# Dashboard_Tester_rev1.net
KiCad netlist of a schematic drawn in EAGLE
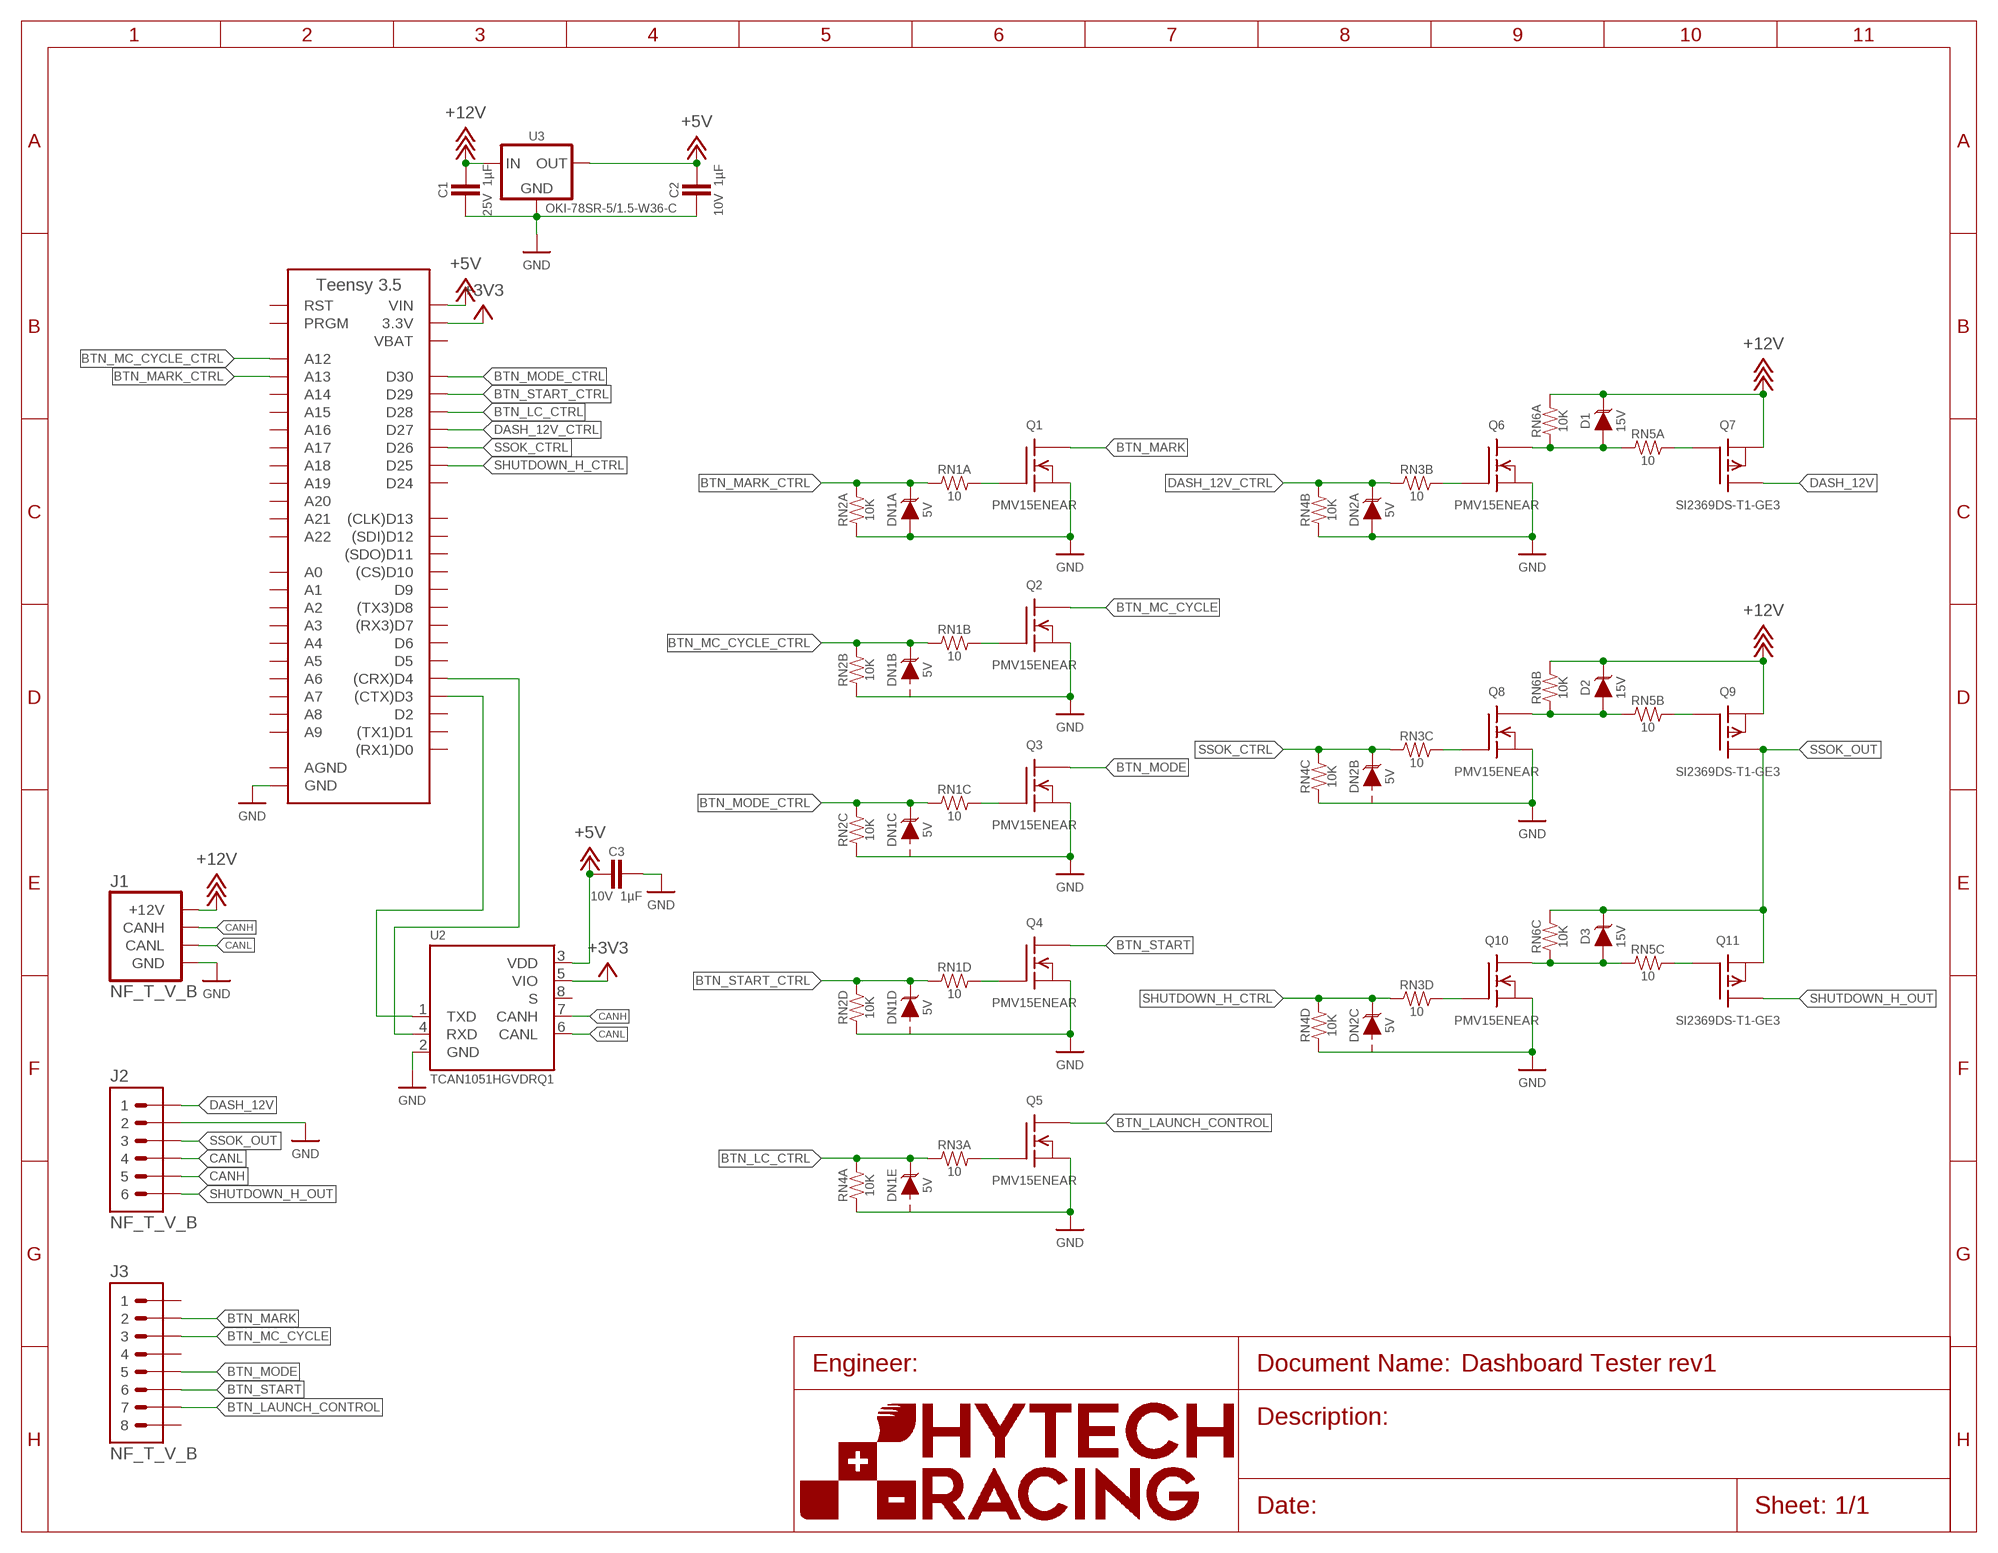
[diagram p0: schematic, sheet 1]

(export (version "E")
  (design (tool "Eeschema 10.0.6"))
  (components
    (comp (ref "C1")
      (value "CAPACITOR_0603_25V_1UF")
      (footprint "eagle-import:0603-CAP")
      (fields
        (field (name "CAPACITANCE") "1µF")
        (field (name "MANUFACTURER") "Samsung Electro-Mechanics")
        (field (name "MPN") "CL10B105KA8NNNC")
        (field (name "TOLERANCE") "10%")
        (field (name "VOLTAGE") "25V")
      )
      (libsource (lib "eagle-import") (part "CAPACITOR_?_060325V_1UF"))
    )
    (comp (ref "C2")
      (value "CAPACITOR_0603_10V_1UF")
      (footprint "eagle-import:0603-CAP")
      (fields
        (field (name "CAPACITANCE") "1µF")
        (field (name "MANUFACTURER") "Yageo")
        (field (name "MPN") "CC0603KRX7R6BB105")
        (field (name "TOLERANCE") "10%")
        (field (name "VOLTAGE") "10V")
      )
      (libsource (lib "eagle-import") (part "CAPACITOR_?_060310V_1UF"))
    )
    (comp (ref "C3")
      (value "CAPACITOR_0603_10V_1UF")
      (footprint "eagle-import:0603-CAP")
      (fields
        (field (name "CAPACITANCE") "1µF")
        (field (name "MANUFACTURER") "Yageo")
        (field (name "MPN") "CC0603KRX7R6BB105")
        (field (name "TOLERANCE") "10%")
        (field (name "VOLTAGE") "10V")
      )
      (libsource (lib "eagle-import") (part "CAPACITOR_?_060310V_1UF"))
    )
    (comp (ref "D1")
      (value "TVS_15V")
      (footprint "eagle-import:SOT-23")
      (fields
        (field (name "MANUFACTURER") "Vishay General Semiconductor - Diodes Division")
        (field (name "MPN") "GSOT15-E3-08")
        (field (name "VOLTAGE") "15V")
      )
      (libsource (lib "eagle-import") (part "TVS_15V"))
    )
    (comp (ref "D2")
      (value "TVS_15V")
      (footprint "eagle-import:SOT-23")
      (fields
        (field (name "MANUFACTURER") "Vishay General Semiconductor - Diodes Division")
        (field (name "MPN") "GSOT15-E3-08")
        (field (name "VOLTAGE") "15V")
      )
      (libsource (lib "eagle-import") (part "TVS_15V"))
    )
    (comp (ref "D3")
      (value "TVS_15V")
      (footprint "eagle-import:SOT-23")
      (fields
        (field (name "MANUFACTURER") "Vishay General Semiconductor - Diodes Division")
        (field (name "MPN") "GSOT15-E3-08")
        (field (name "VOLTAGE") "15V")
      )
      (libsource (lib "eagle-import") (part "TVS_15V"))
    )
    (comp (ref "DN1")
      (value "TVS_ARRAY_5V")
      (footprint "eagle-import:SOT363")
      (fields
        (field (name "MANUFACTURER") "Vishay General Semiconductor - Diodes Division")
        (field (name "MPN") "VESD05A5-06G-G3-08")
        (field (name "VOLTAGE") "5V")
      )
      (libsource (lib "eagle-import") (part "TVS_ARRAY_5V"))
    )
    (comp (ref "DN2")
      (value "TVS_ARRAY_5V")
      (footprint "eagle-import:SOT363")
      (fields
        (field (name "MANUFACTURER") "Vishay General Semiconductor - Diodes Division")
        (field (name "MPN") "VESD05A5-06G-G3-08")
        (field (name "VOLTAGE") "5V")
      )
      (libsource (lib "eagle-import") (part "TVS_ARRAY_5V"))
    )
    (comp (ref "J1")
      (value "CONNECTOR-CAN_NF_T_V_BLACK")
      (footprint "eagle-import:MOLEX_NANOFIT_PTH_04")
      (fields
        (field (name "MANUFACTURER") "Molex")
        (field (name "MODEL") "NF_T_V_B")
        (field (name "MPN") "105429-1304 ")
      )
      (libsource (lib "eagle-import") (part "CONNECTOR-CAN_?_NF_T_VBLACK"))
    )
    (comp (ref "J2")
      (value "CONNECTOR-6_NF_T_V_BLACK")
      (footprint "eagle-import:MOLEX_NANOFIT_PTH_06")
      (fields
        (field (name "MANUFACTURER") "Molex")
        (field (name "MODEL") "NF_T_V_B")
        (field (name "MPN") "105310-1306 ")
      )
      (libsource (lib "eagle-import") (part "CONNECTOR-6_?_NF_T_VBLACK"))
    )
    (comp (ref "J3")
      (value "CONNECTOR-8_NF_T_V_BLACK")
      (footprint "eagle-import:MOLEX_NANOFIT_PTH_08")
      (fields
        (field (name "MANUFACTURER") "Molex")
        (field (name "MODEL") "NF_T_V_B")
        (field (name "MPN") "105310-1308")
      )
      (libsource (lib "eagle-import") (part "CONNECTOR-8_?_NF_T_VBLACK"))
    )
    (comp (ref "Q1")
      (value "TRANSISTOR_N_MOS_PMV15ENEA")
      (footprint "eagle-import:SOT-23")
      (fields (field (name "MANUFACTURER") "Nexperia USA Inc.") (field (name "MPN") "PMV15ENEAR"))
      (libsource (lib "eagle-import") (part "TRANSISTOR_N_MOS_PMV15ENEA"))
    )
    (comp (ref "Q2")
      (value "TRANSISTOR_N_MOS_PMV15ENEA")
      (footprint "eagle-import:SOT-23")
      (fields (field (name "MANUFACTURER") "Nexperia USA Inc.") (field (name "MPN") "PMV15ENEAR"))
      (libsource (lib "eagle-import") (part "TRANSISTOR_N_MOS_PMV15ENEA"))
    )
    (comp (ref "Q3")
      (value "TRANSISTOR_N_MOS_PMV15ENEA")
      (footprint "eagle-import:SOT-23")
      (fields (field (name "MANUFACTURER") "Nexperia USA Inc.") (field (name "MPN") "PMV15ENEAR"))
      (libsource (lib "eagle-import") (part "TRANSISTOR_N_MOS_PMV15ENEA"))
    )
    (comp (ref "Q4")
      (value "TRANSISTOR_N_MOS_PMV15ENEA")
      (footprint "eagle-import:SOT-23")
      (fields (field (name "MANUFACTURER") "Nexperia USA Inc.") (field (name "MPN") "PMV15ENEAR"))
      (libsource (lib "eagle-import") (part "TRANSISTOR_N_MOS_PMV15ENEA"))
    )
    (comp (ref "Q5")
      (value "TRANSISTOR_N_MOS_PMV15ENEA")
      (footprint "eagle-import:SOT-23")
      (fields (field (name "MANUFACTURER") "Nexperia USA Inc.") (field (name "MPN") "PMV15ENEAR"))
      (libsource (lib "eagle-import") (part "TRANSISTOR_N_MOS_PMV15ENEA"))
    )
    (comp (ref "Q6")
      (value "TRANSISTOR_N_MOS_PMV15ENEA")
      (footprint "eagle-import:SOT-23")
      (fields (field (name "MANUFACTURER") "Nexperia USA Inc.") (field (name "MPN") "PMV15ENEAR"))
      (libsource (lib "eagle-import") (part "TRANSISTOR_N_MOS_PMV15ENEA"))
    )
    (comp (ref "Q7")
      (value "TRANSISTOR_P_MOS_SOT23_SI2369DS-T1-GE3")
      (footprint "eagle-import:SOT-23")
      (fields (field (name "MANUFACTURER") "Vishay Siliconix") (field (name "MPN") "SI2369DS-T1-GE3"))
      (libsource (lib "eagle-import") (part "TRANSISTOR_P_MOS_?_SOT23SI2369DS-T1-GE3"))
    )
    (comp (ref "Q8")
      (value "TRANSISTOR_N_MOS_PMV15ENEA")
      (footprint "eagle-import:SOT-23")
      (fields (field (name "MANUFACTURER") "Nexperia USA Inc.") (field (name "MPN") "PMV15ENEAR"))
      (libsource (lib "eagle-import") (part "TRANSISTOR_N_MOS_PMV15ENEA"))
    )
    (comp (ref "Q9")
      (value "TRANSISTOR_P_MOS_SOT23_SI2369DS-T1-GE3")
      (footprint "eagle-import:SOT-23")
      (fields (field (name "MANUFACTURER") "Vishay Siliconix") (field (name "MPN") "SI2369DS-T1-GE3"))
      (libsource (lib "eagle-import") (part "TRANSISTOR_P_MOS_?_SOT23SI2369DS-T1-GE3"))
    )
    (comp (ref "Q10")
      (value "TRANSISTOR_N_MOS_PMV15ENEA")
      (footprint "eagle-import:SOT-23")
      (fields (field (name "MANUFACTURER") "Nexperia USA Inc.") (field (name "MPN") "PMV15ENEAR"))
      (libsource (lib "eagle-import") (part "TRANSISTOR_N_MOS_PMV15ENEA"))
    )
    (comp (ref "Q11")
      (value "TRANSISTOR_P_MOS_SOT23_SI2369DS-T1-GE3")
      (footprint "eagle-import:SOT-23")
      (fields (field (name "MANUFACTURER") "Vishay Siliconix") (field (name "MPN") "SI2369DS-T1-GE3"))
      (libsource (lib "eagle-import") (part "TRANSISTOR_P_MOS_?_SOT23SI2369DS-T1-GE3"))
    )
    (comp (ref "RN1")
      (value "RESISTOR_NETWORK_4_10")
      (footprint "eagle-import:1206-RES")
      (fields
        (field (name "MANUFACTURER") "Bourns Inc.")
        (field (name "MPN") "CAT16-100J4LF")
        (field (name "RESISTANCE") "10")
      )
      (libsource (lib "eagle-import") (part "RESISTOR_NETWORK_4_10"))
    )
    (comp (ref "RN2")
      (value "RESISTOR_NETWORK_4_10K")
      (footprint "eagle-import:1206-RES")
      (fields
        (field (name "MANUFACTURER") "Yageo")
        (field (name "MPN") "TC164-FR-0710KL")
        (field (name "RESISTANCE") "10K")
      )
      (libsource (lib "eagle-import") (part "RESISTOR_NETWORK_4_10K"))
    )
    (comp (ref "RN3")
      (value "RESISTOR_NETWORK_4_10")
      (footprint "eagle-import:1206-RES")
      (fields
        (field (name "MANUFACTURER") "Bourns Inc.")
        (field (name "MPN") "CAT16-100J4LF")
        (field (name "RESISTANCE") "10")
      )
      (libsource (lib "eagle-import") (part "RESISTOR_NETWORK_4_10"))
    )
    (comp (ref "RN4")
      (value "RESISTOR_NETWORK_4_10K")
      (footprint "eagle-import:1206-RES")
      (fields
        (field (name "MANUFACTURER") "Yageo")
        (field (name "MPN") "TC164-FR-0710KL")
        (field (name "RESISTANCE") "10K")
      )
      (libsource (lib "eagle-import") (part "RESISTOR_NETWORK_4_10K"))
    )
    (comp (ref "RN5")
      (value "RESISTOR_NETWORK_4_10")
      (footprint "eagle-import:1206-RES")
      (fields
        (field (name "MANUFACTURER") "Bourns Inc.")
        (field (name "MPN") "CAT16-100J4LF")
        (field (name "RESISTANCE") "10")
      )
      (libsource (lib "eagle-import") (part "RESISTOR_NETWORK_4_10"))
    )
    (comp (ref "RN6")
      (value "RESISTOR_NETWORK_4_10K")
      (footprint "eagle-import:1206-RES")
      (fields
        (field (name "MANUFACTURER") "Yageo")
        (field (name "MPN") "TC164-FR-0710KL")
        (field (name "RESISTANCE") "10K")
      )
      (libsource (lib "eagle-import") (part "RESISTOR_NETWORK_4_10K"))
    )
    (comp (ref "U1")
      (value "TEENSY_3.5")
      (footprint "eagle-import:TEENSY_LONG_EXT")
      (libsource (lib "eagle-import") (part "TEENSY_3.5"))
    )
    (comp (ref "U2")
      (value "CAN_TRANSCIEVER_TCAN1051HQV-Q1")
      (footprint "eagle-import:SOIC-08")
      (fields (field (name "MANUFACTURER") "Texas Instruments") (field (name "MPN") "TCAN1051HGVDRQ1"))
      (libsource (lib "eagle-import") (part "CAN_TRANSCIEVER_TCAN1051V-Q1HQ"))
    )
    (comp (ref "U3")
      (value "VOLTAGE_REGULATOR_OKI-78SR_5V")
      (footprint "eagle-import:OKI-78SR")
      (fields
        (field (name "MANUFACTURER") "Murata Power Solutions Inc.")
        (field (name "MPN") "OKI-78SR-5/1.5-W36-C")
      )
      (libsource (lib "eagle-import") (part "VOLTAGE_REGULATOR_?_OKI-78SR5V"))
    )
  )
  (nets
    (net (code "1") (name "+3V3") (class "Default")
      (node (ref "U1") (pin "3V3") (pinfunction "3.3V_3V3") (pintype "power_in"))
      (node (ref "U1") (pin "3V3@2") (pinfunction "3.3V_3V3@2") (pintype "power_in"))
      (node (ref "U1") (pin "3V3@3") (pinfunction "3.3V_3V3@3") (pintype "power_in"))
      (node (ref "U2") (pin "5") (pinfunction "VIO_5") (pintype "power_in"))
    )
    (net (code "2") (name "+5V") (class "Default")
      (node (ref "C2") (pin "1") (pinfunction "1_1") (pintype "passive"))
      (node (ref "C3") (pin "2") (pinfunction "2_2") (pintype "passive"))
      (node (ref "U1") (pin "VIN") (pinfunction "VIN_VIN") (pintype "power_in"))
      (node (ref "U2") (pin "3") (pinfunction "VDD_3") (pintype "power_in"))
      (node (ref "U3") (pin "3") (pinfunction "OUT_3") (pintype "power_in"))
    )
    (net (code "3") (name "+12V") (class "Default")
      (node (ref "C1") (pin "1") (pinfunction "1_1") (pintype "passive"))
      (node (ref "D1") (pin "3") (pinfunction "C_3") (pintype "passive"))
      (node (ref "D2") (pin "3") (pinfunction "C_3") (pintype "passive"))
      (node (ref "J1") (pin "1") (pinfunction "+12V_1") (pintype "power_in"))
      (node (ref "Q7") (pin "2") (pinfunction "S_2") (pintype "passive"))
      (node (ref "Q9") (pin "2") (pinfunction "S_2") (pintype "passive"))
      (node (ref "RN6") (pin "7") (pinfunction "2_7") (pintype "passive"))
      (node (ref "RN6") (pin "8") (pinfunction "2_8") (pintype "passive"))
      (node (ref "U3") (pin "1") (pinfunction "IN_1") (pintype "power_in"))
    )
    (net (code "4") (name "/AGND") (class "Default")
      (node (ref "U1") (pin "AGND/GND") (pinfunction "AGND_AGND/GND") (pintype "power_in"))
    )
    (net (code "5") (name "/VBAT") (class "Default")
      (node (ref "U1") (pin "VBAT") (pinfunction "VBAT_VBAT") (pintype "power_in"))
    )
    (net (code "6") (name "BTN_LAUNCH_CONTROL") (class "Default")
      (node (ref "J3") (pin "7") (pinfunction "7_7") (pintype "passive"))
      (node (ref "Q5") (pin "3") (pinfunction "D_3") (pintype "passive"))
    )
    (net (code "7") (name "BTN_LC_CTRL") (class "Default")
      (node (ref "DN1") (pin "6") (pinfunction "C_6") (pintype "passive"))
      (node (ref "RN3") (pin "1") (pinfunction "1_1") (pintype "passive"))
      (node (ref "RN4") (pin "8") (pinfunction "2_8") (pintype "passive"))
      (node (ref "U1") (pin "D28") (pinfunction "D28_D28") (pintype "bidirectional"))
    )
    (net (code "8") (name "BTN_MARK") (class "Default")
      (node (ref "J3") (pin "2") (pinfunction "2_2") (pintype "passive"))
      (node (ref "Q1") (pin "3") (pinfunction "D_3") (pintype "passive"))
    )
    (net (code "9") (name "BTN_MARK_CTRL") (class "Default")
      (node (ref "DN1") (pin "1") (pinfunction "C_1") (pintype "passive"))
      (node (ref "RN1") (pin "1") (pinfunction "1_1") (pintype "passive"))
      (node (ref "RN2") (pin "8") (pinfunction "2_8") (pintype "passive"))
      (node (ref "U1") (pin "D32") (pinfunction "A13_D32") (pintype "bidirectional"))
    )
    (net (code "10") (name "BTN_MC_CYCLE") (class "Default")
      (node (ref "J3") (pin "3") (pinfunction "3_3") (pintype "passive"))
      (node (ref "Q2") (pin "3") (pinfunction "D_3") (pintype "passive"))
    )
    (net (code "11") (name "BTN_MC_CYCLE_CTRL") (class "Default")
      (node (ref "DN1") (pin "3") (pinfunction "C_3") (pintype "passive"))
      (node (ref "RN1") (pin "2") (pinfunction "1_2") (pintype "passive"))
      (node (ref "RN2") (pin "7") (pinfunction "2_7") (pintype "passive"))
      (node (ref "U1") (pin "D31") (pinfunction "A12_D31") (pintype "bidirectional"))
    )
    (net (code "12") (name "BTN_MODE") (class "Default")
      (node (ref "J3") (pin "5") (pinfunction "5_5") (pintype "passive"))
      (node (ref "Q3") (pin "3") (pinfunction "D_3") (pintype "passive"))
    )
    (net (code "13") (name "BTN_MODE_CTRL") (class "Default")
      (node (ref "DN1") (pin "4") (pinfunction "C_4") (pintype "passive"))
      (node (ref "RN1") (pin "3") (pinfunction "1_3") (pintype "passive"))
      (node (ref "RN2") (pin "6") (pinfunction "2_6") (pintype "passive"))
      (node (ref "U1") (pin "D30") (pinfunction "D30_D30") (pintype "bidirectional"))
    )
    (net (code "14") (name "BTN_START") (class "Default")
      (node (ref "J3") (pin "6") (pinfunction "6_6") (pintype "passive"))
      (node (ref "Q4") (pin "3") (pinfunction "D_3") (pintype "passive"))
    )
    (net (code "15") (name "BTN_START_CTRL") (class "Default")
      (node (ref "DN1") (pin "5") (pinfunction "C_5") (pintype "passive"))
      (node (ref "RN1") (pin "4") (pinfunction "1_4") (pintype "passive"))
      (node (ref "RN2") (pin "5") (pinfunction "2_5") (pintype "passive"))
      (node (ref "U1") (pin "D29") (pinfunction "D29_D29") (pintype "bidirectional"))
    )
    (net (code "16") (name "CANH") (class "Default")
      (node (ref "J1") (pin "4") (pinfunction "CANH_4") (pintype "bidirectional"))
      (node (ref "J2") (pin "5") (pinfunction "5_5") (pintype "passive"))
      (node (ref "U2") (pin "7") (pinfunction "CANH_7") (pintype "output"))
    )
    (net (code "17") (name "CANL") (class "Default")
      (node (ref "J1") (pin "3") (pinfunction "CANL_3") (pintype "bidirectional"))
      (node (ref "J2") (pin "4") (pinfunction "4_4") (pintype "passive"))
      (node (ref "U2") (pin "6") (pinfunction "CANL_6") (pintype "bidirectional"))
    )
    (net (code "18") (name "DASH_12V") (class "Default")
      (node (ref "J2") (pin "1") (pinfunction "1_1") (pintype "passive"))
      (node (ref "Q7") (pin "3") (pinfunction "D_3") (pintype "passive"))
    )
    (net (code "19") (name "DASH_12V_CTRL") (class "Default")
      (node (ref "DN2") (pin "1") (pinfunction "C_1") (pintype "passive"))
      (node (ref "RN3") (pin "2") (pinfunction "1_2") (pintype "passive"))
      (node (ref "RN4") (pin "7") (pinfunction "2_7") (pintype "passive"))
      (node (ref "U1") (pin "D27") (pinfunction "D27_D27") (pintype "bidirectional"))
    )
    (net (code "20") (name "GND") (class "Default")
      (node (ref "C1") (pin "2") (pinfunction "2_2") (pintype "passive"))
      (node (ref "C2") (pin "2") (pinfunction "2_2") (pintype "passive"))
      (node (ref "C3") (pin "1") (pinfunction "1_1") (pintype "passive"))
      (node (ref "DN1") (pin "2") (pinfunction "A_2") (pintype "passive"))
      (node (ref "DN2") (pin "2") (pinfunction "A_2") (pintype "passive"))
      (node (ref "J1") (pin "2") (pinfunction "GND_2") (pintype "power_in"))
      (node (ref "J2") (pin "2") (pinfunction "2_2") (pintype "passive"))
      (node (ref "Q1") (pin "2") (pinfunction "S_2") (pintype "passive"))
      (node (ref "Q10") (pin "2") (pinfunction "S_2") (pintype "passive"))
      (node (ref "Q2") (pin "2") (pinfunction "S_2") (pintype "passive"))
      (node (ref "Q3") (pin "2") (pinfunction "S_2") (pintype "passive"))
      (node (ref "Q4") (pin "2") (pinfunction "S_2") (pintype "passive"))
      (node (ref "Q5") (pin "2") (pinfunction "S_2") (pintype "passive"))
      (node (ref "Q6") (pin "2") (pinfunction "S_2") (pintype "passive"))
      (node (ref "Q8") (pin "2") (pinfunction "S_2") (pintype "passive"))
      (node (ref "RN2") (pin "1") (pinfunction "1_1") (pintype "passive"))
      (node (ref "RN2") (pin "2") (pinfunction "1_2") (pintype "passive"))
      (node (ref "RN2") (pin "3") (pinfunction "1_3") (pintype "passive"))
      (node (ref "RN2") (pin "4") (pinfunction "1_4") (pintype "passive"))
      (node (ref "RN4") (pin "1") (pinfunction "1_1") (pintype "passive"))
      (node (ref "RN4") (pin "2") (pinfunction "1_2") (pintype "passive"))
      (node (ref "RN4") (pin "3") (pinfunction "1_3") (pintype "passive"))
      (node (ref "RN4") (pin "4") (pinfunction "1_4") (pintype "passive"))
      (node (ref "U1") (pin "GND") (pinfunction "GND_GND") (pintype "power_in"))
      (node (ref "U1") (pin "GND@2") (pinfunction "GND_GND@2") (pintype "power_in"))
      (node (ref "U1") (pin "GND@3") (pinfunction "GND_GND@3") (pintype "power_in"))
      (node (ref "U2") (pin "2") (pinfunction "GND_2") (pintype "power_in"))
      (node (ref "U3") (pin "2") (pinfunction "GND_2") (pintype "power_in"))
    )
    (net (code "21") (name "Net-(D1-A)") (class "Default")
      (node (ref "D1") (pin "1") (pinfunction "A_1") (pintype "passive"))
      (node (ref "Q6") (pin "3") (pinfunction "D_3") (pintype "passive"))
      (node (ref "RN5") (pin "1") (pinfunction "1_1") (pintype "passive"))
      (node (ref "RN6") (pin "1") (pinfunction "1_1") (pintype "passive"))
    )
    (net (code "22") (name "Net-(D2-A)") (class "Default")
      (node (ref "D2") (pin "1") (pinfunction "A_1") (pintype "passive"))
      (node (ref "Q8") (pin "3") (pinfunction "D_3") (pintype "passive"))
      (node (ref "RN5") (pin "2") (pinfunction "1_2") (pintype "passive"))
      (node (ref "RN6") (pin "2") (pinfunction "1_2") (pintype "passive"))
    )
    (net (code "23") (name "Net-(D3-A)") (class "Default")
      (node (ref "D3") (pin "1") (pinfunction "A_1") (pintype "passive"))
      (node (ref "Q10") (pin "3") (pinfunction "D_3") (pintype "passive"))
      (node (ref "RN5") (pin "3") (pinfunction "1_3") (pintype "passive"))
      (node (ref "RN6") (pin "3") (pinfunction "1_3") (pintype "passive"))
    )
    (net (code "24") (name "Net-(Q1-G)") (class "Default")
      (node (ref "Q1") (pin "1") (pinfunction "G_1") (pintype "passive"))
      (node (ref "RN1") (pin "8") (pinfunction "2_8") (pintype "passive"))
    )
    (net (code "25") (name "Net-(Q2-G)") (class "Default")
      (node (ref "Q2") (pin "1") (pinfunction "G_1") (pintype "passive"))
      (node (ref "RN1") (pin "7") (pinfunction "2_7") (pintype "passive"))
    )
    (net (code "26") (name "Net-(Q3-G)") (class "Default")
      (node (ref "Q3") (pin "1") (pinfunction "G_1") (pintype "passive"))
      (node (ref "RN1") (pin "6") (pinfunction "2_6") (pintype "passive"))
    )
    (net (code "27") (name "Net-(Q4-G)") (class "Default")
      (node (ref "Q4") (pin "1") (pinfunction "G_1") (pintype "passive"))
      (node (ref "RN1") (pin "5") (pinfunction "2_5") (pintype "passive"))
    )
    (net (code "28") (name "Net-(Q5-G)") (class "Default")
      (node (ref "Q5") (pin "1") (pinfunction "G_1") (pintype "passive"))
      (node (ref "RN3") (pin "8") (pinfunction "2_8") (pintype "passive"))
    )
    (net (code "29") (name "Net-(Q6-G)") (class "Default")
      (node (ref "Q6") (pin "1") (pinfunction "G_1") (pintype "passive"))
      (node (ref "RN3") (pin "7") (pinfunction "2_7") (pintype "passive"))
    )
    (net (code "30") (name "Net-(Q7-G)") (class "Default")
      (node (ref "Q7") (pin "1") (pinfunction "G_1") (pintype "passive"))
      (node (ref "RN5") (pin "8") (pinfunction "2_8") (pintype "passive"))
    )
    (net (code "31") (name "Net-(Q8-G)") (class "Default")
      (node (ref "Q8") (pin "1") (pinfunction "G_1") (pintype "passive"))
      (node (ref "RN3") (pin "6") (pinfunction "2_6") (pintype "passive"))
    )
    (net (code "32") (name "Net-(Q9-G)") (class "Default")
      (node (ref "Q9") (pin "1") (pinfunction "G_1") (pintype "passive"))
      (node (ref "RN5") (pin "7") (pinfunction "2_7") (pintype "passive"))
    )
    (net (code "33") (name "Net-(Q10-G)") (class "Default")
      (node (ref "Q10") (pin "1") (pinfunction "G_1") (pintype "passive"))
      (node (ref "RN3") (pin "5") (pinfunction "2_5") (pintype "passive"))
    )
    (net (code "34") (name "Net-(Q11-G)") (class "Default")
      (node (ref "Q11") (pin "1") (pinfunction "G_1") (pintype "passive"))
      (node (ref "RN5") (pin "6") (pinfunction "2_6") (pintype "passive"))
    )
    (net (code "35") (name "Net-(U1-(CRX)D4)") (class "Default")
      (node (ref "U1") (pin "D4") (pinfunction "(CRX)D4_D4") (pintype "bidirectional"))
      (node (ref "U2") (pin "4") (pinfunction "RXD_4") (pintype "output"))
    )
    (net (code "36") (name "Net-(U1-(CTX)D3)") (class "Default")
      (node (ref "U1") (pin "D3") (pinfunction "(CTX)D3_D3") (pintype "bidirectional"))
      (node (ref "U2") (pin "1") (pinfunction "TXD_1") (pintype "input"))
    )
    (net (code "37") (name "SHUTDOWN_H_CTRL") (class "Default")
      (node (ref "DN2") (pin "4") (pinfunction "C_4") (pintype "passive"))
      (node (ref "RN3") (pin "4") (pinfunction "1_4") (pintype "passive"))
      (node (ref "RN4") (pin "5") (pinfunction "2_5") (pintype "passive"))
      (node (ref "U1") (pin "D25") (pinfunction "D25_D25") (pintype "bidirectional"))
    )
    (net (code "38") (name "SHUTDOWN_H_OUT") (class "Default")
      (node (ref "J2") (pin "6") (pinfunction "6_6") (pintype "passive"))
      (node (ref "Q11") (pin "3") (pinfunction "D_3") (pintype "passive"))
    )
    (net (code "39") (name "SSOK_CTRL") (class "Default")
      (node (ref "DN2") (pin "3") (pinfunction "C_3") (pintype "passive"))
      (node (ref "RN3") (pin "3") (pinfunction "1_3") (pintype "passive"))
      (node (ref "RN4") (pin "6") (pinfunction "2_6") (pintype "passive"))
      (node (ref "U1") (pin "D26") (pinfunction "D26_D26") (pintype "bidirectional"))
    )
    (net (code "40") (name "SSOK_OUT") (class "Default")
      (node (ref "D3") (pin "3") (pinfunction "C_3") (pintype "passive"))
      (node (ref "J2") (pin "3") (pinfunction "3_3") (pintype "passive"))
      (node (ref "Q11") (pin "2") (pinfunction "S_2") (pintype "passive"))
      (node (ref "Q9") (pin "3") (pinfunction "D_3") (pintype "passive"))
      (node (ref "RN6") (pin "6") (pinfunction "2_6") (pintype "passive"))
    )
    (net (code "41") (name "unconnected-(J3-Pad1)") (class "Default")
      (node (ref "J3") (pin "1") (pinfunction "1_1") (pintype "passive"))
    )
    (net (code "42") (name "unconnected-(J3-Pad4)") (class "Default")
      (node (ref "J3") (pin "4") (pinfunction "4_4") (pintype "passive"))
    )
    (net (code "43") (name "unconnected-(J3-Pad8)") (class "Default")
      (node (ref "J3") (pin "8") (pinfunction "8_8") (pintype "passive"))
    )
    (net (code "44") (name "unconnected-(U1-(CLK)D13-PadD13)") (class "Default")
      (node (ref "U1") (pin "D13") (pinfunction "(CLK)D13_D13") (pintype "bidirectional"))
    )
    (net (code "45") (name "unconnected-(U1-(CS)D10-PadD10)") (class "Default")
      (node (ref "U1") (pin "D10") (pinfunction "(CS)D10_D10") (pintype "bidirectional"))
    )
    (net (code "46") (name "unconnected-(U1-(RX1)D0-PadD0)") (class "Default")
      (node (ref "U1") (pin "D0") (pinfunction "(RX1)D0_D0") (pintype "bidirectional"))
    )
    (net (code "47") (name "unconnected-(U1-(RX3)D7-PadD7)") (class "Default")
      (node (ref "U1") (pin "D7") (pinfunction "(RX3)D7_D7") (pintype "bidirectional"))
    )
    (net (code "48") (name "unconnected-(U1-(SDI)D12-PadD12)") (class "Default")
      (node (ref "U1") (pin "D12") (pinfunction "(SDI)D12_D12") (pintype "bidirectional"))
    )
    (net (code "49") (name "unconnected-(U1-(SDO)D11-PadD11)") (class "Default")
      (node (ref "U1") (pin "D11") (pinfunction "(SDO)D11_D11") (pintype "bidirectional"))
    )
    (net (code "50") (name "unconnected-(U1-(TX1)D1-PadD1)") (class "Default")
      (node (ref "U1") (pin "D1") (pinfunction "(TX1)D1_D1") (pintype "bidirectional"))
    )
    (net (code "51") (name "unconnected-(U1-(TX3)D8-PadD8)") (class "Default")
      (node (ref "U1") (pin "D8") (pinfunction "(TX3)D8_D8") (pintype "bidirectional"))
    )
    (net (code "52") (name "unconnected-(U1-A0-PadD14)") (class "Default")
      (node (ref "U1") (pin "D14") (pinfunction "A0_D14") (pintype "bidirectional"))
    )
    (net (code "53") (name "unconnected-(U1-A1-PadD15)") (class "Default")
      (node (ref "U1") (pin "D15") (pinfunction "A1_D15") (pintype "bidirectional"))
    )
    (net (code "54") (name "unconnected-(U1-A2-PadD16)") (class "Default")
      (node (ref "U1") (pin "D16") (pinfunction "A2_D16") (pintype "bidirectional"))
    )
    (net (code "55") (name "unconnected-(U1-A3-PadD17)") (class "Default")
      (node (ref "U1") (pin "D17") (pinfunction "A3_D17") (pintype "bidirectional"))
    )
    (net (code "56") (name "unconnected-(U1-A4-PadD18)") (class "Default")
      (node (ref "U1") (pin "D18") (pinfunction "A4_D18") (pintype "bidirectional"))
    )
    (net (code "57") (name "unconnected-(U1-A5-PadD19)") (class "Default")
      (node (ref "U1") (pin "D19") (pinfunction "A5_D19") (pintype "bidirectional"))
    )
    (net (code "58") (name "unconnected-(U1-A6-PadD20)") (class "Default")
      (node (ref "U1") (pin "D20") (pinfunction "A6_D20") (pintype "bidirectional"))
    )
    (net (code "59") (name "unconnected-(U1-A7-PadD21)") (class "Default")
      (node (ref "U1") (pin "D21") (pinfunction "A7_D21") (pintype "bidirectional"))
    )
    (net (code "60") (name "unconnected-(U1-A8-PadD22)") (class "Default")
      (node (ref "U1") (pin "D22") (pinfunction "A8_D22") (pintype "bidirectional"))
    )
    (net (code "61") (name "unconnected-(U1-A9-PadD23)") (class "Default")
      (node (ref "U1") (pin "D23") (pinfunction "A9_D23") (pintype "bidirectional"))
    )
    (net (code "62") (name "unconnected-(U1-A14-PadD33)") (class "Default")
      (node (ref "U1") (pin "D33") (pinfunction "A14_D33") (pintype "bidirectional"))
    )
    (net (code "63") (name "unconnected-(U1-A15-PadD34)") (class "Default")
      (node (ref "U1") (pin "D34") (pinfunction "A15_D34") (pintype "bidirectional"))
    )
    (net (code "64") (name "unconnected-(U1-A16-PadD35)") (class "Default")
      (node (ref "U1") (pin "D35") (pinfunction "A16_D35") (pintype "bidirectional"))
    )
    (net (code "65") (name "unconnected-(U1-A17-PadD36)") (class "Default")
      (node (ref "U1") (pin "D36") (pinfunction "A17_D36") (pintype "bidirectional"))
    )
    (net (code "66") (name "unconnected-(U1-A18-PadD37)") (class "Default")
      (node (ref "U1") (pin "D37") (pinfunction "A18_D37") (pintype "bidirectional"))
    )
    (net (code "67") (name "unconnected-(U1-A19-PadD38)") (class "Default")
      (node (ref "U1") (pin "D38") (pinfunction "A19_D38") (pintype "bidirectional"))
    )
    (net (code "68") (name "unconnected-(U1-A20-PadD39)") (class "Default")
      (node (ref "U1") (pin "D39") (pinfunction "A20_D39") (pintype "bidirectional"))
    )
    (net (code "69") (name "unconnected-(U1-A21-PadD40)") (class "Default")
      (node (ref "U1") (pin "D40") (pinfunction "A21_D40") (pintype "bidirectional"))
    )
    (net (code "70") (name "unconnected-(U1-A22-PadD41)") (class "Default")
      (node (ref "U1") (pin "D41") (pinfunction "A22_D41") (pintype "bidirectional"))
    )
    (net (code "71") (name "unconnected-(U1-PadD2)") (class "Default")
      (node (ref "U1") (pin "D2") (pinfunction "D2_D2") (pintype "bidirectional"))
    )
    (net (code "72") (name "unconnected-(U1-PadD5)") (class "Default")
      (node (ref "U1") (pin "D5") (pinfunction "D5_D5") (pintype "bidirectional"))
    )
    (net (code "73") (name "unconnected-(U1-PadD6)") (class "Default")
      (node (ref "U1") (pin "D6") (pinfunction "D6_D6") (pintype "bidirectional"))
    )
    (net (code "74") (name "unconnected-(U1-PadD9)") (class "Default")
      (node (ref "U1") (pin "D9") (pinfunction "D9_D9") (pintype "bidirectional"))
    )
    (net (code "75") (name "unconnected-(U1-PadD24)") (class "Default")
      (node (ref "U1") (pin "D24") (pinfunction "D24_D24") (pintype "bidirectional"))
    )
    (net (code "76") (name "unconnected-(U1-PadPRGM)") (class "Default")
      (node (ref "U1") (pin "PRGM") (pinfunction "PRGM_PRGM") (pintype "bidirectional"))
    )
    (net (code "77") (name "unconnected-(U1-RST-PadON{slash}OFF)") (class "Default")
      (node (ref "U1") (pin "ON/OFF") (pinfunction "RST_ON/OFF") (pintype "bidirectional"))
    )
    (net (code "78") (name "unconnected-(U2-S-Pad8)") (class "Default")
      (node (ref "U2") (pin "8") (pinfunction "S_8") (pintype "input"))
    )
  )
)
